# CON_SODIMM_200PIN_MO-224_NEW.net
KiCad netlist of a schematic drawn in Altium Designer
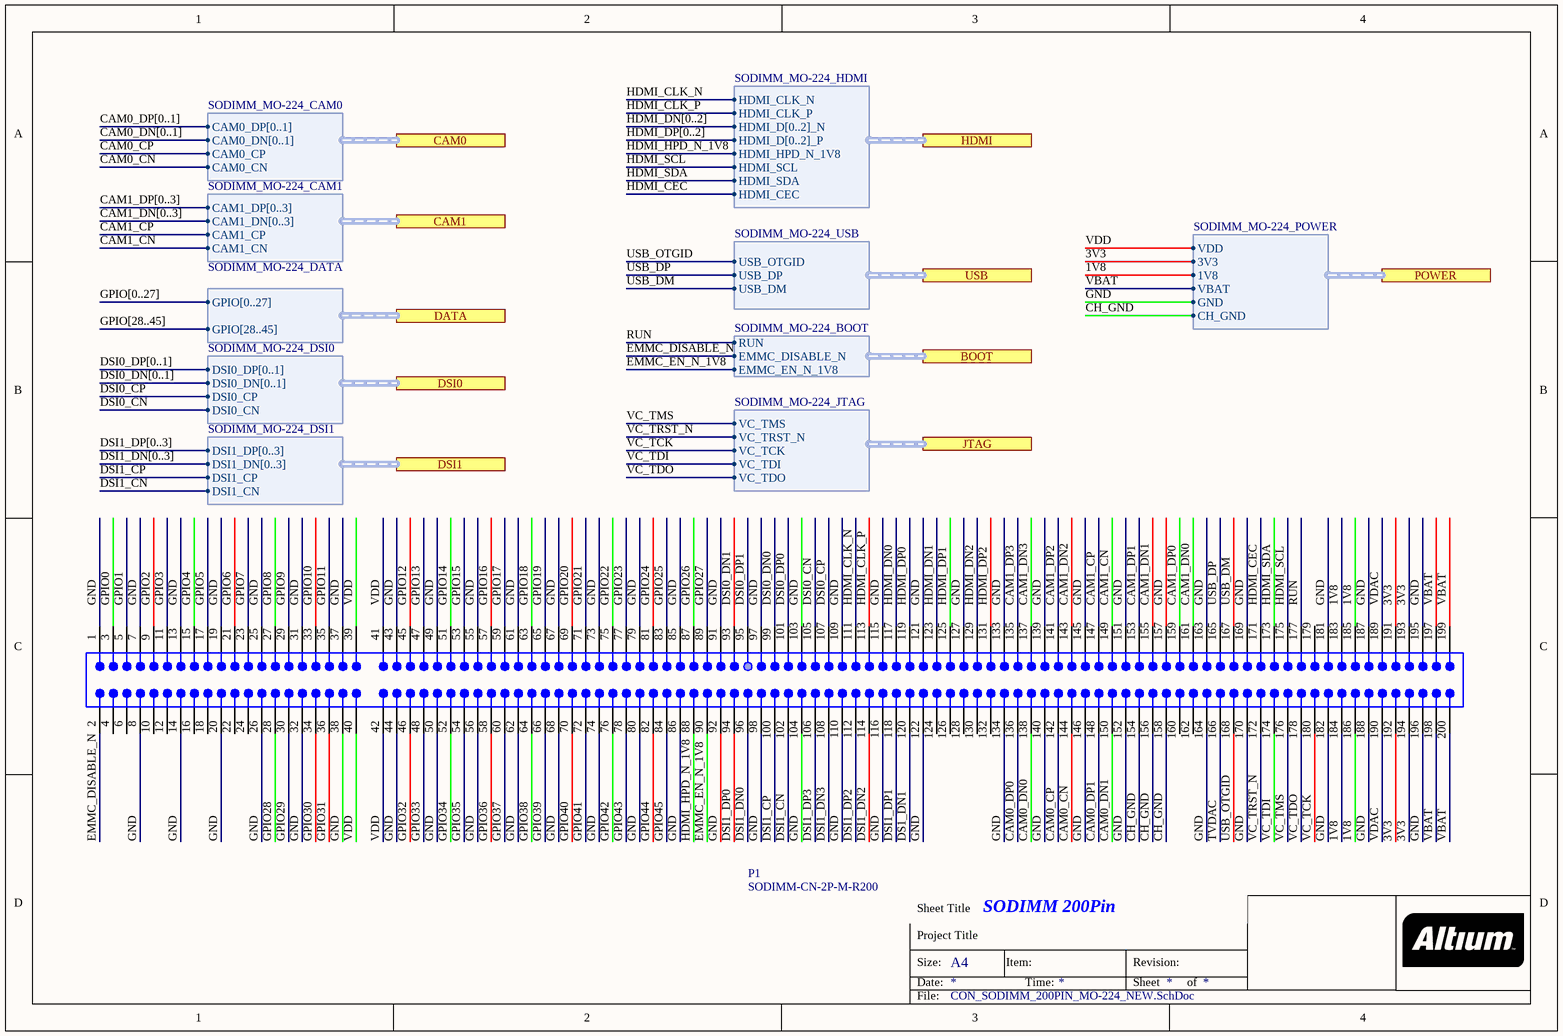
[diagram p0: CON_SODIMM_200PIN_MO-224_NEW.SchDoc]

(export (version "E")
  (design (tool "Eeschema 10.0.6"))
  (components
    (comp (ref "P1")
      (value "SODIMM-CN-2P-M-R200")
      (footprint "SODIMM-GF-2D-600-1K-S200")
      (description "Golden finger, SODIMM, Dual, Staggered, Pitch 0.6mm, 200-Position")
      (fields (field (name "PUBLISHER") "Altium"))
      (libsource (lib "Altium Shanghai") (part "CMP-0001-00060-2"))
    )
  )
  (nets
    (net (code "12") (name "/1V8") (class "Default")
      (node (ref "P1") (pin "183") (pinfunction "183_183") (pintype "passive"))
      (node (ref "P1") (pin "184") (pinfunction "184_184") (pintype "passive"))
      (node (ref "P1") (pin "185") (pinfunction "185_185") (pintype "passive"))
      (node (ref "P1") (pin "186") (pinfunction "186_186") (pintype "passive"))
    )
    (net (code "13") (name "/3V3") (class "Default")
      (node (ref "P1") (pin "191") (pinfunction "191_191") (pintype "passive"))
      (node (ref "P1") (pin "192") (pinfunction "192_192") (pintype "passive"))
      (node (ref "P1") (pin "193") (pinfunction "193_193") (pintype "passive"))
      (node (ref "P1") (pin "194") (pinfunction "194_194") (pintype "passive"))
    )
    (net (code "14") (name "/CAM0_CN") (class "Default")
      (node (ref "P1") (pin "144") (pinfunction "144_144") (pintype "passive"))
    )
    (net (code "15") (name "/CAM0_CP") (class "Default")
      (node (ref "P1") (pin "142") (pinfunction "142_142") (pintype "passive"))
    )
    (net (code "16") (name "/CAM0_DN0") (class "Default")
      (node (ref "P1") (pin "138") (pinfunction "138_138") (pintype "passive"))
    )
    (net (code "17") (name "/CAM0_DN1") (class "Default")
      (node (ref "P1") (pin "150") (pinfunction "150_150") (pintype "passive"))
    )
    (net (code "19") (name "/CAM0_DP0") (class "Default")
      (node (ref "P1") (pin "136") (pinfunction "136_136") (pintype "passive"))
    )
    (net (code "20") (name "/CAM0_DP1") (class "Default")
      (node (ref "P1") (pin "148") (pinfunction "148_148") (pintype "passive"))
    )
    (net (code "22") (name "/CAM1_CN") (class "Default")
      (node (ref "P1") (pin "149") (pinfunction "149_149") (pintype "passive"))
    )
    (net (code "23") (name "/CAM1_CP") (class "Default")
      (node (ref "P1") (pin "147") (pinfunction "147_147") (pintype "passive"))
    )
    (net (code "24") (name "/CAM1_DN0") (class "Default")
      (node (ref "P1") (pin "161") (pinfunction "161_161") (pintype "passive"))
    )
    (net (code "25") (name "/CAM1_DN1") (class "Default")
      (node (ref "P1") (pin "155") (pinfunction "155_155") (pintype "passive"))
    )
    (net (code "26") (name "/CAM1_DN2") (class "Default")
      (node (ref "P1") (pin "143") (pinfunction "143_143") (pintype "passive"))
    )
    (net (code "27") (name "/CAM1_DN3") (class "Default")
      (node (ref "P1") (pin "137") (pinfunction "137_137") (pintype "passive"))
    )
    (net (code "29") (name "/CAM1_DP0") (class "Default")
      (node (ref "P1") (pin "159") (pinfunction "159_159") (pintype "passive"))
    )
    (net (code "30") (name "/CAM1_DP1") (class "Default")
      (node (ref "P1") (pin "153") (pinfunction "153_153") (pintype "passive"))
    )
    (net (code "31") (name "/CAM1_DP2") (class "Default")
      (node (ref "P1") (pin "141") (pinfunction "141_141") (pintype "passive"))
    )
    (net (code "32") (name "/CAM1_DP3") (class "Default")
      (node (ref "P1") (pin "135") (pinfunction "135_135") (pintype "passive"))
    )
    (net (code "34") (name "/CH_GND") (class "Default")
      (node (ref "P1") (pin "154") (pinfunction "154_154") (pintype "passive"))
      (node (ref "P1") (pin "156") (pinfunction "156_156") (pintype "passive"))
      (node (ref "P1") (pin "158") (pinfunction "158_158") (pintype "passive"))
    )
    (net (code "35") (name "/DS1_DN1") (class "Default")
      (node (ref "P1") (pin "120") (pinfunction "120_120") (pintype "passive"))
    )
    (net (code "36") (name "/DSI0_CN") (class "Default")
      (node (ref "P1") (pin "105") (pinfunction "105_105") (pintype "passive"))
    )
    (net (code "37") (name "/DSI0_CP") (class "Default")
      (node (ref "P1") (pin "107") (pinfunction "107_107") (pintype "passive"))
    )
    (net (code "38") (name "/DSI0_DN0") (class "Default")
      (node (ref "P1") (pin "99") (pinfunction "99_99") (pintype "passive"))
    )
    (net (code "39") (name "/DSI0_DN1") (class "Default")
      (node (ref "P1") (pin "93") (pinfunction "93_93") (pintype "passive"))
    )
    (net (code "41") (name "/DSI0_DP0") (class "Default")
      (node (ref "P1") (pin "101") (pinfunction "101_101") (pintype "passive"))
    )
    (net (code "42") (name "/DSI0_DP1") (class "Default")
      (node (ref "P1") (pin "95") (pinfunction "95_95") (pintype "passive"))
    )
    (net (code "44") (name "/DSI1_CN") (class "Default")
      (node (ref "P1") (pin "102") (pinfunction "102_102") (pintype "passive"))
    )
    (net (code "45") (name "/DSI1_CP") (class "Default")
      (node (ref "P1") (pin "100") (pinfunction "100_100") (pintype "passive"))
    )
    (net (code "46") (name "/DSI1_DN0") (class "Default")
      (node (ref "P1") (pin "96") (pinfunction "96_96") (pintype "passive"))
    )
    (net (code "47") (name "/DSI1_DN2") (class "Default")
      (node (ref "P1") (pin "114") (pinfunction "114_114") (pintype "passive"))
    )
    (net (code "48") (name "/DSI1_DN3") (class "Default")
      (node (ref "P1") (pin "108") (pinfunction "108_108") (pintype "passive"))
    )
    (net (code "50") (name "/DSI1_DP0") (class "Default")
      (node (ref "P1") (pin "94") (pinfunction "94_94") (pintype "passive"))
    )
    (net (code "51") (name "/DSI1_DP1") (class "Default")
      (node (ref "P1") (pin "118") (pinfunction "118_118") (pintype "passive"))
    )
    (net (code "52") (name "/DSI1_DP2") (class "Default")
      (node (ref "P1") (pin "112") (pinfunction "112_112") (pintype "passive"))
    )
    (net (code "53") (name "/DSI1_DP3") (class "Default")
      (node (ref "P1") (pin "106") (pinfunction "106_106") (pintype "passive"))
    )
    (net (code "55") (name "/EMMC_DISABLE_N") (class "Default")
      (node (ref "P1") (pin "2") (pinfunction "2_2") (pintype "passive"))
    )
    (net (code "56") (name "/EMMC_EN_N_1V8") (class "Default")
      (node (ref "P1") (pin "90") (pinfunction "90_90") (pintype "passive"))
    )
    (net (code "57") (name "/GND") (class "Default")
      (node (ref "P1") (pin "1") (pinfunction "1_1") (pintype "passive"))
      (node (ref "P1") (pin "103") (pinfunction "103_103") (pintype "passive"))
      (node (ref "P1") (pin "104") (pinfunction "104_104") (pintype "passive"))
      (node (ref "P1") (pin "109") (pinfunction "109_109") (pintype "passive"))
      (node (ref "P1") (pin "110") (pinfunction "110_110") (pintype "passive"))
      (node (ref "P1") (pin "115") (pinfunction "115_115") (pintype "passive"))
      (node (ref "P1") (pin "116") (pinfunction "116_116") (pintype "passive"))
      (node (ref "P1") (pin "121") (pinfunction "121_121") (pintype "passive"))
      (node (ref "P1") (pin "122") (pinfunction "122_122") (pintype "passive"))
      (node (ref "P1") (pin "127") (pinfunction "127_127") (pintype "passive"))
      (node (ref "P1") (pin "13") (pinfunction "13_13") (pintype "passive"))
      (node (ref "P1") (pin "133") (pinfunction "133_133") (pintype "passive"))
      (node (ref "P1") (pin "134") (pinfunction "134_134") (pintype "passive"))
      (node (ref "P1") (pin "139") (pinfunction "139_139") (pintype "passive"))
      (node (ref "P1") (pin "14") (pinfunction "14_14") (pintype "passive"))
      (node (ref "P1") (pin "140") (pinfunction "140_140") (pintype "passive"))
      (node (ref "P1") (pin "145") (pinfunction "145_145") (pintype "passive"))
      (node (ref "P1") (pin "146") (pinfunction "146_146") (pintype "passive"))
      (node (ref "P1") (pin "151") (pinfunction "151_151") (pintype "passive"))
      (node (ref "P1") (pin "152") (pinfunction "152_152") (pintype "passive"))
      (node (ref "P1") (pin "157") (pinfunction "157_157") (pintype "passive"))
      (node (ref "P1") (pin "163") (pinfunction "163_163") (pintype "passive"))
      (node (ref "P1") (pin "164") (pinfunction "164_164") (pintype "passive"))
      (node (ref "P1") (pin "169") (pinfunction "169_169") (pintype "passive"))
      (node (ref "P1") (pin "170") (pinfunction "170_170") (pintype "passive"))
      (node (ref "P1") (pin "181") (pinfunction "181_181") (pintype "passive"))
      (node (ref "P1") (pin "182") (pinfunction "182_182") (pintype "passive"))
      (node (ref "P1") (pin "187") (pinfunction "187_187") (pintype "passive"))
      (node (ref "P1") (pin "188") (pinfunction "188_188") (pintype "passive"))
      (node (ref "P1") (pin "19") (pinfunction "19_19") (pintype "passive"))
      (node (ref "P1") (pin "195") (pinfunction "195_195") (pintype "passive"))
      (node (ref "P1") (pin "196") (pinfunction "196_196") (pintype "passive"))
      (node (ref "P1") (pin "20") (pinfunction "20_20") (pintype "passive"))
      (node (ref "P1") (pin "25") (pinfunction "25_25") (pintype "passive"))
      (node (ref "P1") (pin "26") (pinfunction "26_26") (pintype "passive"))
      (node (ref "P1") (pin "31") (pinfunction "31_31") (pintype "passive"))
      (node (ref "P1") (pin "32") (pinfunction "32_32") (pintype "passive"))
      (node (ref "P1") (pin "37") (pinfunction "37_37") (pintype "passive"))
      (node (ref "P1") (pin "38") (pinfunction "38_38") (pintype "passive"))
      (node (ref "P1") (pin "43") (pinfunction "43_43") (pintype "passive"))
      (node (ref "P1") (pin "44") (pinfunction "44_44") (pintype "passive"))
      (node (ref "P1") (pin "49") (pinfunction "49_49") (pintype "passive"))
      (node (ref "P1") (pin "50") (pinfunction "50_50") (pintype "passive"))
      (node (ref "P1") (pin "55") (pinfunction "55_55") (pintype "passive"))
      (node (ref "P1") (pin "56") (pinfunction "56_56") (pintype "passive"))
      (node (ref "P1") (pin "61") (pinfunction "61_61") (pintype "passive"))
      (node (ref "P1") (pin "62") (pinfunction "62_62") (pintype "passive"))
      (node (ref "P1") (pin "67") (pinfunction "67_67") (pintype "passive"))
      (node (ref "P1") (pin "68") (pinfunction "68_68") (pintype "passive"))
      (node (ref "P1") (pin "7") (pinfunction "7_7") (pintype "passive"))
      (node (ref "P1") (pin "73") (pinfunction "73_73") (pintype "passive"))
      (node (ref "P1") (pin "74") (pinfunction "74_74") (pintype "passive"))
      (node (ref "P1") (pin "79") (pinfunction "79_79") (pintype "passive"))
      (node (ref "P1") (pin "8") (pinfunction "8_8") (pintype "passive"))
      (node (ref "P1") (pin "80") (pinfunction "80_80") (pintype "passive"))
      (node (ref "P1") (pin "85") (pinfunction "85_85") (pintype "passive"))
      (node (ref "P1") (pin "86") (pinfunction "86_86") (pintype "passive"))
      (node (ref "P1") (pin "91") (pinfunction "91_91") (pintype "passive"))
      (node (ref "P1") (pin "92") (pinfunction "92_92") (pintype "passive"))
      (node (ref "P1") (pin "97") (pinfunction "97_97") (pintype "passive"))
      (node (ref "P1") (pin "98") (pinfunction "98_98") (pintype "passive"))
    )
    (net (code "58") (name "/GPIO0") (class "Default")
      (node (ref "P1") (pin "3") (pinfunction "3_3") (pintype "passive"))
    )
    (net (code "59") (name "/GPIO1") (class "Default")
      (node (ref "P1") (pin "5") (pinfunction "5_5") (pintype "passive"))
    )
    (net (code "60") (name "/GPIO2") (class "Default")
      (node (ref "P1") (pin "9") (pinfunction "9_9") (pintype "passive"))
    )
    (net (code "61") (name "/GPIO3") (class "Default")
      (node (ref "P1") (pin "11") (pinfunction "11_11") (pintype "passive"))
    )
    (net (code "62") (name "/GPIO4") (class "Default")
      (node (ref "P1") (pin "15") (pinfunction "15_15") (pintype "passive"))
    )
    (net (code "63") (name "/GPIO5") (class "Default")
      (node (ref "P1") (pin "17") (pinfunction "17_17") (pintype "passive"))
    )
    (net (code "64") (name "/GPIO6") (class "Default")
      (node (ref "P1") (pin "21") (pinfunction "21_21") (pintype "passive"))
    )
    (net (code "65") (name "/GPIO7") (class "Default")
      (node (ref "P1") (pin "23") (pinfunction "23_23") (pintype "passive"))
    )
    (net (code "66") (name "/GPIO8") (class "Default")
      (node (ref "P1") (pin "27") (pinfunction "27_27") (pintype "passive"))
    )
    (net (code "67") (name "/GPIO9") (class "Default")
      (node (ref "P1") (pin "29") (pinfunction "29_29") (pintype "passive"))
    )
    (net (code "68") (name "/GPIO10") (class "Default")
      (node (ref "P1") (pin "33") (pinfunction "33_33") (pintype "passive"))
    )
    (net (code "69") (name "/GPIO11") (class "Default")
      (node (ref "P1") (pin "35") (pinfunction "35_35") (pintype "passive"))
    )
    (net (code "70") (name "/GPIO12") (class "Default")
      (node (ref "P1") (pin "45") (pinfunction "45_45") (pintype "passive"))
    )
    (net (code "71") (name "/GPIO13") (class "Default")
      (node (ref "P1") (pin "47") (pinfunction "47_47") (pintype "passive"))
    )
    (net (code "72") (name "/GPIO14") (class "Default")
      (node (ref "P1") (pin "51") (pinfunction "51_51") (pintype "passive"))
    )
    (net (code "73") (name "/GPIO15") (class "Default")
      (node (ref "P1") (pin "53") (pinfunction "53_53") (pintype "passive"))
    )
    (net (code "74") (name "/GPIO16") (class "Default")
      (node (ref "P1") (pin "57") (pinfunction "57_57") (pintype "passive"))
    )
    (net (code "75") (name "/GPIO17") (class "Default")
      (node (ref "P1") (pin "59") (pinfunction "59_59") (pintype "passive"))
    )
    (net (code "76") (name "/GPIO18") (class "Default")
      (node (ref "P1") (pin "63") (pinfunction "63_63") (pintype "passive"))
    )
    (net (code "77") (name "/GPIO19") (class "Default")
      (node (ref "P1") (pin "65") (pinfunction "65_65") (pintype "passive"))
    )
    (net (code "78") (name "/GPIO20") (class "Default")
      (node (ref "P1") (pin "69") (pinfunction "69_69") (pintype "passive"))
    )
    (net (code "79") (name "/GPIO21") (class "Default")
      (node (ref "P1") (pin "71") (pinfunction "71_71") (pintype "passive"))
    )
    (net (code "80") (name "/GPIO22") (class "Default")
      (node (ref "P1") (pin "75") (pinfunction "75_75") (pintype "passive"))
    )
    (net (code "81") (name "/GPIO23") (class "Default")
      (node (ref "P1") (pin "77") (pinfunction "77_77") (pintype "passive"))
    )
    (net (code "82") (name "/GPIO24") (class "Default")
      (node (ref "P1") (pin "81") (pinfunction "81_81") (pintype "passive"))
    )
    (net (code "83") (name "/GPIO25") (class "Default")
      (node (ref "P1") (pin "83") (pinfunction "83_83") (pintype "passive"))
    )
    (net (code "84") (name "/GPIO26") (class "Default")
      (node (ref "P1") (pin "87") (pinfunction "87_87") (pintype "passive"))
    )
    (net (code "85") (name "/GPIO27") (class "Default")
      (node (ref "P1") (pin "89") (pinfunction "89_89") (pintype "passive"))
    )
    (net (code "86") (name "/GPIO28") (class "Default")
      (node (ref "P1") (pin "28") (pinfunction "28_28") (pintype "passive"))
    )
    (net (code "87") (name "/GPIO29") (class "Default")
      (node (ref "P1") (pin "30") (pinfunction "30_30") (pintype "passive"))
    )
    (net (code "88") (name "/GPIO30") (class "Default")
      (node (ref "P1") (pin "34") (pinfunction "34_34") (pintype "passive"))
    )
    (net (code "89") (name "/GPIO31") (class "Default")
      (node (ref "P1") (pin "36") (pinfunction "36_36") (pintype "passive"))
    )
    (net (code "90") (name "/GPIO32") (class "Default")
      (node (ref "P1") (pin "46") (pinfunction "46_46") (pintype "passive"))
    )
    (net (code "91") (name "/GPIO33") (class "Default")
      (node (ref "P1") (pin "48") (pinfunction "48_48") (pintype "passive"))
    )
    (net (code "92") (name "/GPIO34") (class "Default")
      (node (ref "P1") (pin "52") (pinfunction "52_52") (pintype "passive"))
    )
    (net (code "93") (name "/GPIO35") (class "Default")
      (node (ref "P1") (pin "54") (pinfunction "54_54") (pintype "passive"))
    )
    (net (code "94") (name "/GPIO36") (class "Default")
      (node (ref "P1") (pin "58") (pinfunction "58_58") (pintype "passive"))
    )
    (net (code "95") (name "/GPIO37") (class "Default")
      (node (ref "P1") (pin "60") (pinfunction "60_60") (pintype "passive"))
    )
    (net (code "96") (name "/GPIO38") (class "Default")
      (node (ref "P1") (pin "64") (pinfunction "64_64") (pintype "passive"))
    )
    (net (code "97") (name "/GPIO39") (class "Default")
      (node (ref "P1") (pin "66") (pinfunction "66_66") (pintype "passive"))
    )
    (net (code "98") (name "/GPIO40") (class "Default")
      (node (ref "P1") (pin "70") (pinfunction "70_70") (pintype "passive"))
    )
    (net (code "99") (name "/GPIO41") (class "Default")
      (node (ref "P1") (pin "72") (pinfunction "72_72") (pintype "passive"))
    )
    (net (code "100") (name "/GPIO42") (class "Default")
      (node (ref "P1") (pin "76") (pinfunction "76_76") (pintype "passive"))
    )
    (net (code "101") (name "/GPIO43") (class "Default")
      (node (ref "P1") (pin "78") (pinfunction "78_78") (pintype "passive"))
    )
    (net (code "102") (name "/GPIO44") (class "Default")
      (node (ref "P1") (pin "82") (pinfunction "82_82") (pintype "passive"))
    )
    (net (code "103") (name "/GPIO45") (class "Default")
      (node (ref "P1") (pin "84") (pinfunction "84_84") (pintype "passive"))
    )
    (net (code "106") (name "/HDMI_CEC") (class "Default")
      (node (ref "P1") (pin "171") (pinfunction "171_171") (pintype "passive"))
    )
    (net (code "107") (name "/HDMI_CLK_N") (class "Default")
      (node (ref "P1") (pin "111") (pinfunction "111_111") (pintype "passive"))
    )
    (net (code "108") (name "/HDMI_CLK_P") (class "Default")
      (node (ref "P1") (pin "113") (pinfunction "113_113") (pintype "passive"))
    )
    (net (code "109") (name "/HDMI_DN0") (class "Default")
      (node (ref "P1") (pin "117") (pinfunction "117_117") (pintype "passive"))
    )
    (net (code "110") (name "/HDMI_DN1") (class "Default")
      (node (ref "P1") (pin "123") (pinfunction "123_123") (pintype "passive"))
    )
    (net (code "111") (name "/HDMI_DN2") (class "Default")
      (node (ref "P1") (pin "129") (pinfunction "129_129") (pintype "passive"))
    )
    (net (code "112") (name "/HDMI_DP0") (class "Default")
      (node (ref "P1") (pin "119") (pinfunction "119_119") (pintype "passive"))
    )
    (net (code "113") (name "/HDMI_DP1") (class "Default")
      (node (ref "P1") (pin "125") (pinfunction "125_125") (pintype "passive"))
    )
    (net (code "114") (name "/HDMI_DP2") (class "Default")
      (node (ref "P1") (pin "131") (pinfunction "131_131") (pintype "passive"))
    )
    (net (code "116") (name "/HDMI_HPD_N_1V8") (class "Default")
      (node (ref "P1") (pin "88") (pinfunction "88_88") (pintype "passive"))
    )
    (net (code "117") (name "/HDMI_SCL") (class "Default")
      (node (ref "P1") (pin "175") (pinfunction "175_175") (pintype "passive"))
    )
    (net (code "118") (name "/HDMI_SDA") (class "Default")
      (node (ref "P1") (pin "173") (pinfunction "173_173") (pintype "passive"))
    )
    (net (code "120") (name "/RUN") (class "Default")
      (node (ref "P1") (pin "177") (pinfunction "177_177") (pintype "passive"))
    )
    (net (code "121") (name "/TVDAC") (class "Default")
      (node (ref "P1") (pin "166") (pinfunction "166_166") (pintype "passive"))
    )
    (net (code "122") (name "/USB_DM") (class "Default")
      (node (ref "P1") (pin "167") (pinfunction "167_167") (pintype "passive"))
    )
    (net (code "123") (name "/USB_DP") (class "Default")
      (node (ref "P1") (pin "165") (pinfunction "165_165") (pintype "passive"))
    )
    (net (code "124") (name "/USB_OTGID") (class "Default")
      (node (ref "P1") (pin "168") (pinfunction "168_168") (pintype "passive"))
    )
    (net (code "125") (name "/VBAT") (class "Default")
      (node (ref "P1") (pin "197") (pinfunction "197_197") (pintype "passive"))
      (node (ref "P1") (pin "198") (pinfunction "198_198") (pintype "passive"))
      (node (ref "P1") (pin "199") (pinfunction "199_199") (pintype "passive"))
      (node (ref "P1") (pin "200") (pinfunction "200_200") (pintype "passive"))
    )
    (net (code "126") (name "/VC_TCK") (class "Default")
      (node (ref "P1") (pin "180") (pinfunction "180_180") (pintype "passive"))
    )
    (net (code "127") (name "/VC_TDI") (class "Default")
      (node (ref "P1") (pin "174") (pinfunction "174_174") (pintype "passive"))
    )
    (net (code "128") (name "/VC_TDO") (class "Default")
      (node (ref "P1") (pin "178") (pinfunction "178_178") (pintype "passive"))
    )
    (net (code "129") (name "/VC_TMS") (class "Default")
      (node (ref "P1") (pin "176") (pinfunction "176_176") (pintype "passive"))
    )
    (net (code "130") (name "/VC_TRST_N") (class "Default")
      (node (ref "P1") (pin "172") (pinfunction "172_172") (pintype "passive"))
    )
    (net (code "131") (name "/VDAC") (class "Default")
      (node (ref "P1") (pin "189") (pinfunction "189_189") (pintype "passive"))
      (node (ref "P1") (pin "190") (pinfunction "190_190") (pintype "passive"))
    )
    (net (code "132") (name "/VDD") (class "Default")
      (node (ref "P1") (pin "39") (pinfunction "39_39") (pintype "passive"))
      (node (ref "P1") (pin "40") (pinfunction "40_40") (pintype "passive"))
      (node (ref "P1") (pin "41") (pinfunction "41_41") (pintype "passive"))
      (node (ref "P1") (pin "42") (pinfunction "42_42") (pintype "passive"))
    )
    (net (code "143") (name "unconnected-(P1-Pad4)") (class "Default")
      (node (ref "P1") (pin "4") (pinfunction "4_4") (pintype "passive"))
    )
    (net (code "144") (name "unconnected-(P1-Pad6)") (class "Default")
      (node (ref "P1") (pin "6") (pinfunction "6_6") (pintype "passive"))
    )
    (net (code "145") (name "unconnected-(P1-Pad10)") (class "Default")
      (node (ref "P1") (pin "10") (pinfunction "10_10") (pintype "passive"))
    )
    (net (code "146") (name "unconnected-(P1-Pad12)") (class "Default")
      (node (ref "P1") (pin "12") (pinfunction "12_12") (pintype "passive"))
    )
    (net (code "147") (name "unconnected-(P1-Pad16)") (class "Default")
      (node (ref "P1") (pin "16") (pinfunction "16_16") (pintype "passive"))
    )
    (net (code "148") (name "unconnected-(P1-Pad18)") (class "Default")
      (node (ref "P1") (pin "18") (pinfunction "18_18") (pintype "passive"))
    )
    (net (code "149") (name "unconnected-(P1-Pad22)") (class "Default")
      (node (ref "P1") (pin "22") (pinfunction "22_22") (pintype "passive"))
    )
    (net (code "150") (name "unconnected-(P1-Pad24)") (class "Default")
      (node (ref "P1") (pin "24") (pinfunction "24_24") (pintype "passive"))
    )
    (net (code "151") (name "unconnected-(P1-Pad124)") (class "Default")
      (node (ref "P1") (pin "124") (pinfunction "124_124") (pintype "passive"))
    )
    (net (code "152") (name "unconnected-(P1-Pad126)") (class "Default")
      (node (ref "P1") (pin "126") (pinfunction "126_126") (pintype "passive"))
    )
    (net (code "153") (name "unconnected-(P1-Pad128)") (class "Default")
      (node (ref "P1") (pin "128") (pinfunction "128_128") (pintype "passive"))
    )
    (net (code "154") (name "unconnected-(P1-Pad130)") (class "Default")
      (node (ref "P1") (pin "130") (pinfunction "130_130") (pintype "passive"))
    )
    (net (code "155") (name "unconnected-(P1-Pad132)") (class "Default")
      (node (ref "P1") (pin "132") (pinfunction "132_132") (pintype "passive"))
    )
    (net (code "156") (name "unconnected-(P1-Pad160)") (class "Default")
      (node (ref "P1") (pin "160") (pinfunction "160_160") (pintype "passive"))
    )
    (net (code "157") (name "unconnected-(P1-Pad162)") (class "Default")
      (node (ref "P1") (pin "162") (pinfunction "162_162") (pintype "passive"))
    )
    (net (code "158") (name "unconnected-(P1-Pad179)") (class "Default")
      (node (ref "P1") (pin "179") (pinfunction "179_179") (pintype "passive"))
    )
  )
)
